# 9xVoice_MikeB_TH_v1.net
KiCad netlist of a schematic drawn in EAGLE
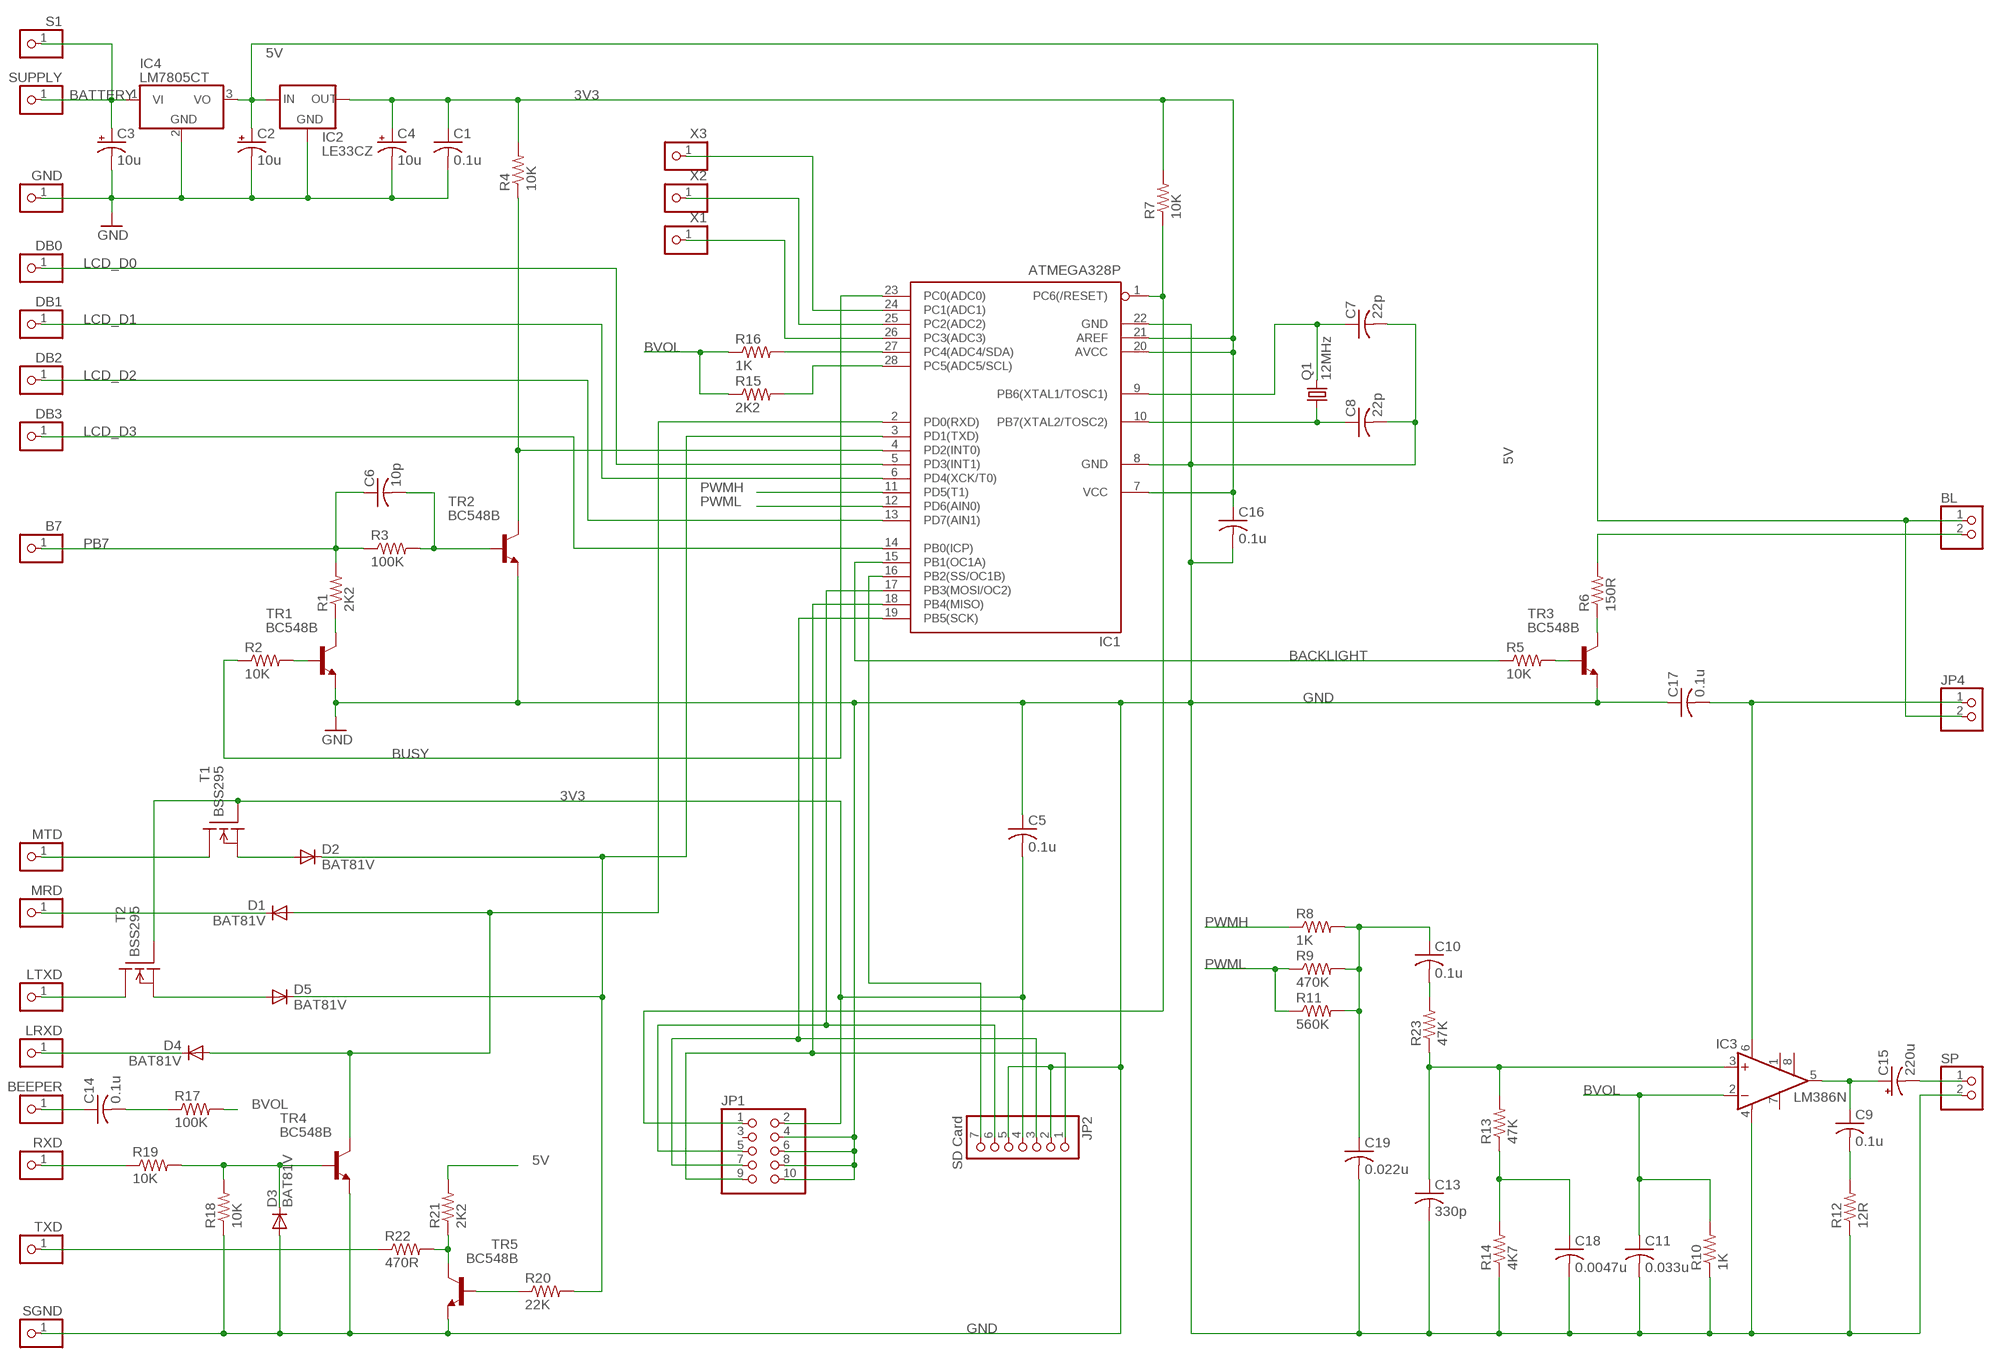
[diagram p0: schematic, sheet 1]

(export (version "E")
  (design (tool "Eeschema 10.0.6"))
  (components
    (comp (ref "B7")
      (value "PINHD-1X1")
      (footprint "eagle-import:1X01")
      (libsource (lib "eagle-import") (part "PINHD-1X1"))
    )
    (comp (ref "BEEPER")
      (value "PINHD-1X1")
      (footprint "eagle-import:1X01")
      (libsource (lib "eagle-import") (part "PINHD-1X1"))
    )
    (comp (ref "BL")
      (value "PINHD-1X2")
      (footprint "eagle-import:1X02")
      (libsource (lib "eagle-import") (part "PINHD-1X2"))
    )
    (comp (ref "C1")
      (value "0.1u")
      (footprint "eagle-import:C025-024X044")
      (libsource (lib "eagle-import") (part "C-US025-024X044"))
    )
    (comp (ref "C2")
      (value "10u")
      (footprint "eagle-import:E1,8-4")
      (libsource (lib "eagle-import") (part "CPOL-USE1.8-4"))
    )
    (comp (ref "C3")
      (value "10u")
      (footprint "eagle-import:E1,8-4")
      (libsource (lib "eagle-import") (part "CPOL-USE1.8-4"))
    )
    (comp (ref "C4")
      (value "10u")
      (footprint "eagle-import:E1,8-4")
      (libsource (lib "eagle-import") (part "CPOL-USE1.8-4"))
    )
    (comp (ref "C5")
      (value "0.1u")
      (footprint "eagle-import:C025-024X044")
      (libsource (lib "eagle-import") (part "C-US025-024X044"))
    )
    (comp (ref "C6")
      (value "10p")
      (footprint "eagle-import:C025-024X044")
      (libsource (lib "eagle-import") (part "C-US025-024X044"))
    )
    (comp (ref "C7")
      (value "22p")
      (footprint "eagle-import:C025-024X044")
      (libsource (lib "eagle-import") (part "C-US025-024X044"))
    )
    (comp (ref "C8")
      (value "22p")
      (footprint "eagle-import:C025-024X044")
      (libsource (lib "eagle-import") (part "C-US025-024X044"))
    )
    (comp (ref "C9")
      (value "0.1u")
      (footprint "eagle-import:C025-024X044")
      (libsource (lib "eagle-import") (part "C-US025-024X044"))
    )
    (comp (ref "C10")
      (value "0.1u")
      (footprint "eagle-import:C025-024X044")
      (libsource (lib "eagle-import") (part "C-US025-024X044"))
    )
    (comp (ref "C11")
      (value "0.033u")
      (footprint "eagle-import:C025-024X044")
      (libsource (lib "eagle-import") (part "C-US025-024X044"))
    )
    (comp (ref "C13")
      (value "330p")
      (footprint "eagle-import:C025-024X044")
      (libsource (lib "eagle-import") (part "C-US025-024X044"))
    )
    (comp (ref "C14")
      (value "0.1u")
      (footprint "eagle-import:C025-024X044")
      (libsource (lib "eagle-import") (part "C-US025-024X044"))
    )
    (comp (ref "C15")
      (value "220u")
      (footprint "eagle-import:E2,5-7")
      (libsource (lib "eagle-import") (part "CPOL-USE2.5-7"))
    )
    (comp (ref "C16")
      (value "0.1u")
      (footprint "eagle-import:C025-024X044")
      (libsource (lib "eagle-import") (part "C-US025-024X044"))
    )
    (comp (ref "C17")
      (value "0.1u")
      (footprint "eagle-import:C025-024X044")
      (libsource (lib "eagle-import") (part "C-US025-024X044"))
    )
    (comp (ref "C18")
      (value "0.0047u")
      (footprint "eagle-import:C025-024X044")
      (libsource (lib "eagle-import") (part "C-US025-024X044"))
    )
    (comp (ref "C19")
      (value "0.022u")
      (footprint "eagle-import:C025-024X044")
      (libsource (lib "eagle-import") (part "C-US025-024X044"))
    )
    (comp (ref "D1")
      (value "BAT81V")
      (footprint "eagle-import:D-2.5")
      (libsource (lib "eagle-import") (part "DIODE-D-2.5"))
    )
    (comp (ref "D2")
      (value "BAT81V")
      (footprint "eagle-import:D-2.5")
      (libsource (lib "eagle-import") (part "DIODE-D-2.5"))
    )
    (comp (ref "D3")
      (value "BAT81V")
      (footprint "eagle-import:D-2.5")
      (libsource (lib "eagle-import") (part "DIODE-D-2.5"))
    )
    (comp (ref "D4")
      (value "BAT81V")
      (footprint "eagle-import:D-2.5")
      (libsource (lib "eagle-import") (part "DIODE-D-2.5"))
    )
    (comp (ref "D5")
      (value "BAT81V")
      (footprint "eagle-import:D-2.5")
      (libsource (lib "eagle-import") (part "DIODE-D-2.5"))
    )
    (comp (ref "DB0")
      (value "PINHD-1X1")
      (footprint "eagle-import:1X01")
      (libsource (lib "eagle-import") (part "PINHD-1X1"))
    )
    (comp (ref "DB1")
      (value "PINHD-1X1")
      (footprint "eagle-import:1X01")
      (libsource (lib "eagle-import") (part "PINHD-1X1"))
    )
    (comp (ref "DB2")
      (value "PINHD-1X1")
      (footprint "eagle-import:1X01")
      (libsource (lib "eagle-import") (part "PINHD-1X1"))
    )
    (comp (ref "DB3")
      (value "PINHD-1X1")
      (footprint "eagle-import:1X01")
      (libsource (lib "eagle-import") (part "PINHD-1X1"))
    )
    (comp (ref "GND")
      (value "PINHD-1X1")
      (footprint "eagle-import:1X01")
      (libsource (lib "eagle-import") (part "PINHD-1X1"))
    )
    (comp (ref "IC1")
      (value "ATMEGA328P")
      (footprint "eagle-import:DIL28-3")
      (libsource (lib "eagle-import") (part "MEGA8-P"))
    )
    (comp (ref "IC2")
      (value "LE33CZ")
      (footprint "eagle-import:78LXX")
      (libsource (lib "eagle-import") (part "78LXX"))
    )
    (comp (ref "IC3")
      (value "LM386N")
      (footprint "eagle-import:DIL08")
      (libsource (lib "eagle-import") (part "LM386?-N1"))
    )
    (comp (ref "IC4")
      (value "LM7805CT")
      (footprint "eagle-import:TO220H")
      (libsource (lib "eagle-import") (part "78T05"))
    )
    (comp (ref "JP1")
      (value "PINHD-2X5")
      (footprint "eagle-import:2X05")
      (libsource (lib "eagle-import") (part "PINHD-2X5"))
    )
    (comp (ref "JP2")
      (value "SD Card")
      (footprint "eagle-import:1X07")
      (libsource (lib "eagle-import") (part "PINHD-1X7"))
    )
    (comp (ref "JP4")
      (value "PINHD-1X2")
      (footprint "eagle-import:1X02")
      (libsource (lib "eagle-import") (part "PINHD-1X2"))
    )
    (comp (ref "LRXD")
      (value "PINHD-1X1")
      (footprint "eagle-import:1X01")
      (libsource (lib "eagle-import") (part "PINHD-1X1"))
    )
    (comp (ref "LTXD")
      (value "PINHD-1X1")
      (footprint "eagle-import:1X01")
      (libsource (lib "eagle-import") (part "PINHD-1X1"))
    )
    (comp (ref "MRD")
      (value "PINHD-1X1")
      (footprint "eagle-import:1X01")
      (libsource (lib "eagle-import") (part "PINHD-1X1"))
    )
    (comp (ref "MTD")
      (value "PINHD-1X1")
      (footprint "eagle-import:1X01")
      (libsource (lib "eagle-import") (part "PINHD-1X1"))
    )
    (comp (ref "Q1")
      (value "12MHz")
      (footprint "eagle-import:HC49_S")
      (libsource (lib "eagle-import") (part "CRYSTALHC49S"))
    )
    (comp (ref "R1")
      (value "2K2")
      (footprint "eagle-import:0207_2V")
      (libsource (lib "eagle-import") (part "R-US_0207/2V"))
    )
    (comp (ref "R2")
      (value "10K")
      (footprint "eagle-import:0207_10")
      (libsource (lib "eagle-import") (part "R-US_0207/10"))
    )
    (comp (ref "R3")
      (value "100K")
      (footprint "eagle-import:0207_2V")
      (libsource (lib "eagle-import") (part "R-US_0207/2V"))
    )
    (comp (ref "R4")
      (value "10K")
      (footprint "eagle-import:0207_2V")
      (libsource (lib "eagle-import") (part "R-US_0207/2V"))
    )
    (comp (ref "R5")
      (value "10K")
      (footprint "eagle-import:0207_2V")
      (libsource (lib "eagle-import") (part "R-US_0207/2V"))
    )
    (comp (ref "R6")
      (value "150R")
      (footprint "eagle-import:0207_2V")
      (libsource (lib "eagle-import") (part "R-US_0207/2V"))
    )
    (comp (ref "R7")
      (value "10K")
      (footprint "eagle-import:0207_2V")
      (libsource (lib "eagle-import") (part "R-US_0207/2V"))
    )
    (comp (ref "R8")
      (value "1K")
      (footprint "eagle-import:0207_2V")
      (libsource (lib "eagle-import") (part "R-US_0207/2V"))
    )
    (comp (ref "R9")
      (value "470K")
      (footprint "eagle-import:0207_2V")
      (libsource (lib "eagle-import") (part "R-US_0207/2V"))
    )
    (comp (ref "R10")
      (value "1K")
      (footprint "eagle-import:0207_2V")
      (libsource (lib "eagle-import") (part "R-US_0207/2V"))
    )
    (comp (ref "R11")
      (value "560K")
      (footprint "eagle-import:0207_2V")
      (libsource (lib "eagle-import") (part "R-US_0207/2V"))
    )
    (comp (ref "R12")
      (value "12R")
      (footprint "eagle-import:0207_2V")
      (libsource (lib "eagle-import") (part "R-US_0207/2V"))
    )
    (comp (ref "R13")
      (value "47K")
      (footprint "eagle-import:0207_2V")
      (libsource (lib "eagle-import") (part "R-US_0207/2V"))
    )
    (comp (ref "R14")
      (value "4K7")
      (footprint "eagle-import:0207_2V")
      (libsource (lib "eagle-import") (part "R-US_0207/2V"))
    )
    (comp (ref "R15")
      (value "2K2")
      (footprint "eagle-import:0207_2V")
      (libsource (lib "eagle-import") (part "R-US_0207/2V"))
    )
    (comp (ref "R16")
      (value "1K")
      (footprint "eagle-import:0207_2V")
      (libsource (lib "eagle-import") (part "R-US_0207/2V"))
    )
    (comp (ref "R17")
      (value "100K")
      (footprint "eagle-import:0207_2V")
      (libsource (lib "eagle-import") (part "R-US_0207/2V"))
    )
    (comp (ref "R18")
      (value "10K")
      (footprint "eagle-import:0207_2V")
      (libsource (lib "eagle-import") (part "R-US_0207/2V"))
    )
    (comp (ref "R19")
      (value "10K")
      (footprint "eagle-import:0207_2V")
      (libsource (lib "eagle-import") (part "R-US_0207/2V"))
    )
    (comp (ref "R20")
      (value "22K")
      (footprint "eagle-import:0207_2V")
      (libsource (lib "eagle-import") (part "R-US_0207/2V"))
    )
    (comp (ref "R21")
      (value "2K2")
      (footprint "eagle-import:0207_2V")
      (libsource (lib "eagle-import") (part "R-US_0207/2V"))
    )
    (comp (ref "R22")
      (value "470R")
      (footprint "eagle-import:0207_2V")
      (libsource (lib "eagle-import") (part "R-US_0207/2V"))
    )
    (comp (ref "R23")
      (value "47K")
      (footprint "eagle-import:0207_2V")
      (libsource (lib "eagle-import") (part "R-US_0207/2V"))
    )
    (comp (ref "RXD")
      (value "PINHD-1X1")
      (footprint "eagle-import:1X01")
      (libsource (lib "eagle-import") (part "PINHD-1X1"))
    )
    (comp (ref "S1")
      (value "PINHD-1X1")
      (footprint "eagle-import:1X01")
      (libsource (lib "eagle-import") (part "PINHD-1X1"))
    )
    (comp (ref "SGND")
      (value "PINHD-1X1")
      (footprint "eagle-import:1X01")
      (libsource (lib "eagle-import") (part "PINHD-1X1"))
    )
    (comp (ref "SP")
      (value "PINHD-1X2")
      (footprint "eagle-import:1X02")
      (libsource (lib "eagle-import") (part "PINHD-1X2"))
    )
    (comp (ref "SUPPLY")
      (value "PINHD-1X1")
      (footprint "eagle-import:1X01")
      (libsource (lib "eagle-import") (part "PINHD-1X1"))
    )
    (comp (ref "T1")
      (value "BSS295")
      (footprint "eagle-import:TO92")
      (libsource (lib "eagle-import") (part "BSS295"))
    )
    (comp (ref "T2")
      (value "BSS295")
      (footprint "eagle-import:TO92")
      (libsource (lib "eagle-import") (part "BSS295"))
    )
    (comp (ref "TR1")
      (value "BC548B")
      (footprint "eagle-import:TO92-EBC")
      (libsource (lib "eagle-import") (part "BC548B"))
    )
    (comp (ref "TR2")
      (value "BC548B")
      (footprint "eagle-import:TO92-EBC")
      (libsource (lib "eagle-import") (part "BC548B"))
    )
    (comp (ref "TR3")
      (value "BC548B")
      (footprint "eagle-import:TO92-EBC")
      (libsource (lib "eagle-import") (part "BC548B"))
    )
    (comp (ref "TR4")
      (value "BC548B")
      (footprint "eagle-import:TO92-EBC")
      (libsource (lib "eagle-import") (part "BC548B"))
    )
    (comp (ref "TR5")
      (value "BC548B")
      (footprint "eagle-import:TO92-EBC")
      (libsource (lib "eagle-import") (part "BC548B"))
    )
    (comp (ref "TXD")
      (value "PINHD-1X1")
      (footprint "eagle-import:1X01")
      (libsource (lib "eagle-import") (part "PINHD-1X1"))
    )
    (comp (ref "X1")
      (value "PINHD-1X1")
      (footprint "eagle-import:1X01")
      (libsource (lib "eagle-import") (part "PINHD-1X1"))
    )
    (comp (ref "X2")
      (value "PINHD-1X1")
      (footprint "eagle-import:1X01")
      (libsource (lib "eagle-import") (part "PINHD-1X1"))
    )
    (comp (ref "X3")
      (value "PINHD-1X1")
      (footprint "eagle-import:1X01")
      (libsource (lib "eagle-import") (part "PINHD-1X1"))
    )
  )
  (nets
    (net (code "1") (name "/3V3") (class "Default")
      (node (ref "C1") (pin "1") (pinfunction "1_1") (pintype "passive"))
      (node (ref "C16") (pin "1") (pinfunction "1_1") (pintype "passive"))
      (node (ref "C4") (pin "+") (pinfunction "+_+") (pintype "passive"))
      (node (ref "C5") (pin "2") (pinfunction "2_2") (pintype "passive"))
      (node (ref "IC1") (pin "20") (pinfunction "AVCC_20") (pintype "power_in"))
      (node (ref "IC1") (pin "21") (pinfunction "AREF_21") (pintype "passive"))
      (node (ref "IC1") (pin "7") (pinfunction "VCC_7") (pintype "power_in"))
      (node (ref "IC2") (pin "OUT") (pinfunction "OUT_OUT") (pintype "passive"))
      (node (ref "JP1") (pin "2") (pinfunction "2_2") (pintype "passive"))
      (node (ref "JP2") (pin "4") (pinfunction "4_4") (pintype "passive"))
      (node (ref "R4") (pin "2") (pinfunction "2_2") (pintype "passive"))
      (node (ref "R7") (pin "2") (pinfunction "2_2") (pintype "passive"))
      (node (ref "T1") (pin "1") (pinfunction "G_1") (pintype "passive"))
      (node (ref "T2") (pin "1") (pinfunction "G_1") (pintype "passive"))
    )
    (net (code "2") (name "/5V") (class "Default")
      (node (ref "BL") (pin "1") (pinfunction "1_1") (pintype "passive"))
      (node (ref "C2") (pin "+") (pinfunction "+_+") (pintype "passive"))
      (node (ref "IC2") (pin "IN") (pinfunction "IN_IN") (pintype "input"))
      (node (ref "IC4") (pin "3") (pinfunction "VO_3") (pintype "passive"))
      (node (ref "JP4") (pin "2") (pinfunction "2_2") (pintype "passive"))
      (node (ref "R21") (pin "2") (pinfunction "2_2") (pintype "passive"))
    )
    (net (code "3") (name "/BACKLIGHT") (class "Default")
      (node (ref "IC1") (pin "15") (pinfunction "PB1(OC1A)_15") (pintype "bidirectional"))
      (node (ref "R5") (pin "1") (pinfunction "1_1") (pintype "passive"))
    )
    (net (code "4") (name "/BATTERY") (class "Default")
      (node (ref "C3") (pin "+") (pinfunction "+_+") (pintype "passive"))
      (node (ref "IC4") (pin "1") (pinfunction "VI_1") (pintype "input"))
      (node (ref "S1") (pin "1") (pinfunction "1_1") (pintype "passive"))
      (node (ref "SUPPLY") (pin "1") (pinfunction "1_1") (pintype "passive"))
    )
    (net (code "5") (name "/BUSY") (class "Default")
      (node (ref "IC1") (pin "23") (pinfunction "PC0(ADC0)_23") (pintype "bidirectional"))
      (node (ref "R2") (pin "1") (pinfunction "1_1") (pintype "passive"))
    )
    (net (code "6") (name "/BVOL") (class "Default")
      (node (ref "C11") (pin "1") (pinfunction "1_1") (pintype "passive"))
      (node (ref "IC3") (pin "2") (pinfunction "-IN_2") (pintype "input"))
      (node (ref "R10") (pin "2") (pinfunction "2_2") (pintype "passive"))
      (node (ref "R15") (pin "1") (pinfunction "1_1") (pintype "passive"))
      (node (ref "R16") (pin "1") (pinfunction "1_1") (pintype "passive"))
      (node (ref "R17") (pin "2") (pinfunction "2_2") (pintype "passive"))
    )
    (net (code "7") (name "/LCD_D0") (class "Default")
      (node (ref "DB0") (pin "1") (pinfunction "1_1") (pintype "passive"))
      (node (ref "IC1") (pin "5") (pinfunction "PD3(INT1)_5") (pintype "bidirectional"))
    )
    (net (code "8") (name "/LCD_D1") (class "Default")
      (node (ref "DB1") (pin "1") (pinfunction "1_1") (pintype "passive"))
      (node (ref "IC1") (pin "6") (pinfunction "PD4(XCK/T0)_6") (pintype "bidirectional"))
    )
    (net (code "9") (name "/LCD_D2") (class "Default")
      (node (ref "DB2") (pin "1") (pinfunction "1_1") (pintype "passive"))
      (node (ref "IC1") (pin "13") (pinfunction "PD7(AIN1)_13") (pintype "bidirectional"))
    )
    (net (code "10") (name "/LCD_D3") (class "Default")
      (node (ref "DB3") (pin "1") (pinfunction "1_1") (pintype "passive"))
      (node (ref "IC1") (pin "14") (pinfunction "PB0(ICP)_14") (pintype "bidirectional"))
    )
    (net (code "11") (name "/PB7") (class "Default")
      (node (ref "B7") (pin "1") (pinfunction "1_1") (pintype "passive"))
      (node (ref "C6") (pin "1") (pinfunction "1_1") (pintype "passive"))
      (node (ref "R1") (pin "2") (pinfunction "2_2") (pintype "passive"))
      (node (ref "R3") (pin "1") (pinfunction "1_1") (pintype "passive"))
    )
    (net (code "12") (name "/PWMH") (class "Default")
      (node (ref "IC1") (pin "11") (pinfunction "PD5(T1)_11") (pintype "bidirectional"))
      (node (ref "R8") (pin "1") (pinfunction "1_1") (pintype "passive"))
    )
    (net (code "13") (name "/PWML") (class "Default")
      (node (ref "IC1") (pin "12") (pinfunction "PD6(AIN0)_12") (pintype "bidirectional"))
      (node (ref "R11") (pin "1") (pinfunction "1_1") (pintype "passive"))
      (node (ref "R9") (pin "1") (pinfunction "1_1") (pintype "passive"))
    )
    (net (code "14") (name "GND") (class "Default")
      (node (ref "C1") (pin "2") (pinfunction "2_2") (pintype "passive"))
      (node (ref "C11") (pin "2") (pinfunction "2_2") (pintype "passive"))
      (node (ref "C13") (pin "2") (pinfunction "2_2") (pintype "passive"))
      (node (ref "C16") (pin "2") (pinfunction "2_2") (pintype "passive"))
      (node (ref "C17") (pin "1") (pinfunction "1_1") (pintype "passive"))
      (node (ref "C18") (pin "2") (pinfunction "2_2") (pintype "passive"))
      (node (ref "C19") (pin "2") (pinfunction "2_2") (pintype "passive"))
      (node (ref "C2") (pin "-") (pinfunction "-_-") (pintype "passive"))
      (node (ref "C3") (pin "-") (pinfunction "-_-") (pintype "passive"))
      (node (ref "C4") (pin "-") (pinfunction "-_-") (pintype "passive"))
      (node (ref "C5") (pin "1") (pinfunction "1_1") (pintype "passive"))
      (node (ref "C7") (pin "2") (pinfunction "2_2") (pintype "passive"))
      (node (ref "C8") (pin "2") (pinfunction "2_2") (pintype "passive"))
      (node (ref "D3") (pin "A") (pinfunction "A_A") (pintype "passive"))
      (node (ref "GND") (pin "1") (pinfunction "1_1") (pintype "passive"))
      (node (ref "IC1") (pin "22") (pinfunction "GND_22") (pintype "power_in"))
      (node (ref "IC1") (pin "8") (pinfunction "GND_8") (pintype "power_in"))
      (node (ref "IC2") (pin "GND") (pinfunction "GND_GND") (pintype "input"))
      (node (ref "IC3") (pin "4") (pinfunction "GND_4") (pintype "power_in"))
      (node (ref "IC4") (pin "2") (pinfunction "GND_2") (pintype "passive"))
      (node (ref "JP1") (pin "10") (pinfunction "10_10") (pintype "passive"))
      (node (ref "JP1") (pin "4") (pinfunction "4_4") (pintype "passive"))
      (node (ref "JP1") (pin "6") (pinfunction "6_6") (pintype "passive"))
      (node (ref "JP1") (pin "8") (pinfunction "8_8") (pintype "passive"))
      (node (ref "JP2") (pin "2") (pinfunction "2_2") (pintype "passive"))
      (node (ref "JP2") (pin "5") (pinfunction "5_5") (pintype "passive"))
      (node (ref "R10") (pin "1") (pinfunction "1_1") (pintype "passive"))
      (node (ref "R12") (pin "1") (pinfunction "1_1") (pintype "passive"))
      (node (ref "R14") (pin "1") (pinfunction "1_1") (pintype "passive"))
      (node (ref "R18") (pin "1") (pinfunction "1_1") (pintype "passive"))
      (node (ref "SGND") (pin "1") (pinfunction "1_1") (pintype "passive"))
      (node (ref "SP") (pin "2") (pinfunction "2_2") (pintype "passive"))
      (node (ref "TR1") (pin "E") (pinfunction "E_E") (pintype "passive"))
      (node (ref "TR2") (pin "E") (pinfunction "E_E") (pintype "passive"))
      (node (ref "TR3") (pin "E") (pinfunction "E_E") (pintype "passive"))
      (node (ref "TR4") (pin "E") (pinfunction "E_E") (pintype "passive"))
      (node (ref "TR5") (pin "E") (pinfunction "E_E") (pintype "passive"))
    )
    (net (code "15") (name "Net-(BEEPER-Pad1)") (class "Default")
      (node (ref "BEEPER") (pin "1") (pinfunction "1_1") (pintype "passive"))
      (node (ref "C14") (pin "1") (pinfunction "1_1") (pintype "passive"))
    )
    (net (code "16") (name "Net-(BL-Pad2)") (class "Default")
      (node (ref "BL") (pin "2") (pinfunction "2_2") (pintype "passive"))
      (node (ref "R6") (pin "2") (pinfunction "2_2") (pintype "passive"))
    )
    (net (code "17") (name "Net-(C6-Pad2)") (class "Default")
      (node (ref "C6") (pin "2") (pinfunction "2_2") (pintype "passive"))
      (node (ref "R3") (pin "2") (pinfunction "2_2") (pintype "passive"))
      (node (ref "TR2") (pin "B") (pinfunction "B_B") (pintype "passive"))
    )
    (net (code "18") (name "Net-(C9-Pad2)") (class "Default")
      (node (ref "C9") (pin "2") (pinfunction "2_2") (pintype "passive"))
      (node (ref "R12") (pin "2") (pinfunction "2_2") (pintype "passive"))
    )
    (net (code "19") (name "Net-(C10-Pad1)") (class "Default")
      (node (ref "C10") (pin "1") (pinfunction "1_1") (pintype "passive"))
      (node (ref "C19") (pin "1") (pinfunction "1_1") (pintype "passive"))
      (node (ref "R11") (pin "2") (pinfunction "2_2") (pintype "passive"))
      (node (ref "R8") (pin "2") (pinfunction "2_2") (pintype "passive"))
      (node (ref "R9") (pin "2") (pinfunction "2_2") (pintype "passive"))
    )
    (net (code "20") (name "Net-(C10-Pad2)") (class "Default")
      (node (ref "C10") (pin "2") (pinfunction "2_2") (pintype "passive"))
      (node (ref "R23") (pin "2") (pinfunction "2_2") (pintype "passive"))
    )
    (net (code "21") (name "Net-(C14-Pad2)") (class "Default")
      (node (ref "C14") (pin "2") (pinfunction "2_2") (pintype "passive"))
      (node (ref "R17") (pin "1") (pinfunction "1_1") (pintype "passive"))
    )
    (net (code "22") (name "Net-(C15-Pad-)") (class "Default")
      (node (ref "C15") (pin "-") (pinfunction "-_-") (pintype "passive"))
      (node (ref "SP") (pin "1") (pinfunction "1_1") (pintype "passive"))
    )
    (net (code "23") (name "Net-(C18-Pad1)") (class "Default")
      (node (ref "C18") (pin "1") (pinfunction "1_1") (pintype "passive"))
      (node (ref "R13") (pin "1") (pinfunction "1_1") (pintype "passive"))
      (node (ref "R14") (pin "2") (pinfunction "2_2") (pintype "passive"))
    )
    (net (code "24") (name "Net-(D1-PadC)") (class "Default")
      (node (ref "D1") (pin "C") (pinfunction "C_C") (pintype "passive"))
      (node (ref "MRD") (pin "1") (pinfunction "1_1") (pintype "passive"))
    )
    (net (code "25") (name "Net-(D3-PadC)") (class "Default")
      (node (ref "D3") (pin "C") (pinfunction "C_C") (pintype "passive"))
      (node (ref "R18") (pin "2") (pinfunction "2_2") (pintype "passive"))
      (node (ref "R19") (pin "2") (pinfunction "2_2") (pintype "passive"))
      (node (ref "TR4") (pin "B") (pinfunction "B_B") (pintype "passive"))
    )
    (net (code "26") (name "Net-(D4-PadC)") (class "Default")
      (node (ref "D4") (pin "C") (pinfunction "C_C") (pintype "passive"))
      (node (ref "LRXD") (pin "1") (pinfunction "1_1") (pintype "passive"))
    )
    (net (code "27") (name "Net-(IC1-PB2(SS{slash}OC1B))") (class "Default")
      (node (ref "IC1") (pin "16") (pinfunction "PB2(SS/OC1B)_16") (pintype "bidirectional"))
      (node (ref "JP2") (pin "7") (pinfunction "7_7") (pintype "passive"))
    )
    (net (code "28") (name "Net-(IC1-PB3(MOSI{slash}OC2))") (class "Default")
      (node (ref "IC1") (pin "17") (pinfunction "PB3(MOSI/OC2)_17") (pintype "bidirectional"))
      (node (ref "JP1") (pin "5") (pinfunction "5_5") (pintype "passive"))
      (node (ref "JP2") (pin "6") (pinfunction "6_6") (pintype "passive"))
    )
    (net (code "29") (name "Net-(IC1-PB4(MISO))") (class "Default")
      (node (ref "IC1") (pin "18") (pinfunction "PB4(MISO)_18") (pintype "bidirectional"))
      (node (ref "JP1") (pin "9") (pinfunction "9_9") (pintype "passive"))
      (node (ref "JP2") (pin "1") (pinfunction "1_1") (pintype "passive"))
    )
    (net (code "30") (name "Net-(IC1-PB5(SCK))") (class "Default")
      (node (ref "IC1") (pin "19") (pinfunction "PB5(SCK)_19") (pintype "bidirectional"))
      (node (ref "JP1") (pin "7") (pinfunction "7_7") (pintype "passive"))
      (node (ref "JP2") (pin "3") (pinfunction "3_3") (pintype "passive"))
    )
    (net (code "31") (name "Net-(IC1-PB6(XTAL1{slash}TOSC1))") (class "Default")
      (node (ref "C7") (pin "1") (pinfunction "1_1") (pintype "passive"))
      (node (ref "IC1") (pin "9") (pinfunction "PB6(XTAL1/TOSC1)_9") (pintype "bidirectional"))
      (node (ref "Q1") (pin "2") (pinfunction "2_2") (pintype "passive"))
    )
    (net (code "32") (name "Net-(IC1-PB7(XTAL2{slash}TOSC2))") (class "Default")
      (node (ref "C8") (pin "1") (pinfunction "1_1") (pintype "passive"))
      (node (ref "IC1") (pin "10") (pinfunction "PB7(XTAL2/TOSC2)_10") (pintype "bidirectional"))
      (node (ref "Q1") (pin "1") (pinfunction "1_1") (pintype "passive"))
    )
    (net (code "33") (name "Net-(IC1-PC1(ADC1))") (class "Default")
      (node (ref "IC1") (pin "24") (pinfunction "PC1(ADC1)_24") (pintype "bidirectional"))
      (node (ref "X3") (pin "1") (pinfunction "1_1") (pintype "passive"))
    )
    (net (code "34") (name "Net-(IC1-PC2(ADC2))") (class "Default")
      (node (ref "IC1") (pin "25") (pinfunction "PC2(ADC2)_25") (pintype "bidirectional"))
      (node (ref "X2") (pin "1") (pinfunction "1_1") (pintype "passive"))
    )
    (net (code "35") (name "Net-(IC1-PC3(ADC3))") (class "Default")
      (node (ref "IC1") (pin "26") (pinfunction "PC3(ADC3)_26") (pintype "bidirectional"))
      (node (ref "X1") (pin "1") (pinfunction "1_1") (pintype "passive"))
    )
    (net (code "36") (name "Net-(IC1-PC4(ADC4{slash}SDA))") (class "Default")
      (node (ref "IC1") (pin "27") (pinfunction "PC4(ADC4/SDA)_27") (pintype "bidirectional"))
      (node (ref "R16") (pin "2") (pinfunction "2_2") (pintype "passive"))
    )
    (net (code "37") (name "Net-(IC1-PC5(ADC5{slash}SCL))") (class "Default")
      (node (ref "IC1") (pin "28") (pinfunction "PC5(ADC5/SCL)_28") (pintype "bidirectional"))
      (node (ref "R15") (pin "2") (pinfunction "2_2") (pintype "passive"))
    )
    (net (code "38") (name "Net-(IC1-PC6({slash}RESET))") (class "Default")
      (node (ref "IC1") (pin "1") (pinfunction "PC6(/RESET)_1") (pintype "bidirectional"))
      (node (ref "JP1") (pin "1") (pinfunction "1_1") (pintype "passive"))
      (node (ref "R7") (pin "1") (pinfunction "1_1") (pintype "passive"))
    )
    (net (code "39") (name "Net-(IC1-PD0(RXD))") (class "Default")
      (node (ref "D1") (pin "A") (pinfunction "A_A") (pintype "passive"))
      (node (ref "D4") (pin "A") (pinfunction "A_A") (pintype "passive"))
      (node (ref "IC1") (pin "2") (pinfunction "PD0(RXD)_2") (pintype "bidirectional"))
      (node (ref "TR4") (pin "C") (pinfunction "C_C") (pintype "passive"))
    )
    (net (code "40") (name "Net-(IC1-PD1(TXD))") (class "Default")
      (node (ref "D2") (pin "C") (pinfunction "C_C") (pintype "passive"))
      (node (ref "D5") (pin "C") (pinfunction "C_C") (pintype "passive"))
      (node (ref "IC1") (pin "3") (pinfunction "PD1(TXD)_3") (pintype "bidirectional"))
      (node (ref "R20") (pin "2") (pinfunction "2_2") (pintype "passive"))
    )
    (net (code "41") (name "Net-(IC1-PD2(INT0))") (class "Default")
      (node (ref "IC1") (pin "4") (pinfunction "PD2(INT0)_4") (pintype "bidirectional"))
      (node (ref "R4") (pin "1") (pinfunction "1_1") (pintype "passive"))
      (node (ref "TR2") (pin "C") (pinfunction "C_C") (pintype "passive"))
    )
    (net (code "42") (name "Net-(IC3-+IN)") (class "Default")
      (node (ref "C13") (pin "1") (pinfunction "1_1") (pintype "passive"))
      (node (ref "IC3") (pin "3") (pinfunction "+IN_3") (pintype "input"))
      (node (ref "R13") (pin "2") (pinfunction "2_2") (pintype "passive"))
      (node (ref "R23") (pin "1") (pinfunction "1_1") (pintype "passive"))
    )
    (net (code "43") (name "Net-(IC3-OUT)") (class "Default")
      (node (ref "C15") (pin "+") (pinfunction "+_+") (pintype "passive"))
      (node (ref "C9") (pin "1") (pinfunction "1_1") (pintype "passive"))
      (node (ref "IC3") (pin "5") (pinfunction "OUT_5") (pintype "output"))
    )
    (net (code "44") (name "Net-(IC3-VS)") (class "Default")
      (node (ref "C17") (pin "2") (pinfunction "2_2") (pintype "passive"))
      (node (ref "IC3") (pin "6") (pinfunction "VS_6") (pintype "power_in"))
      (node (ref "JP4") (pin "1") (pinfunction "1_1") (pintype "passive"))
    )
    (net (code "45") (name "Net-(R1-Pad1)") (class "Default")
      (node (ref "R1") (pin "1") (pinfunction "1_1") (pintype "passive"))
      (node (ref "TR1") (pin "C") (pinfunction "C_C") (pintype "passive"))
    )
    (net (code "46") (name "Net-(R2-Pad2)") (class "Default")
      (node (ref "R2") (pin "2") (pinfunction "2_2") (pintype "passive"))
      (node (ref "TR1") (pin "B") (pinfunction "B_B") (pintype "passive"))
    )
    (net (code "47") (name "Net-(R5-Pad2)") (class "Default")
      (node (ref "R5") (pin "2") (pinfunction "2_2") (pintype "passive"))
      (node (ref "TR3") (pin "B") (pinfunction "B_B") (pintype "passive"))
    )
    (net (code "48") (name "Net-(R6-Pad1)") (class "Default")
      (node (ref "R6") (pin "1") (pinfunction "1_1") (pintype "passive"))
      (node (ref "TR3") (pin "C") (pinfunction "C_C") (pintype "passive"))
    )
    (net (code "49") (name "Net-(R19-Pad1)") (class "Default")
      (node (ref "R19") (pin "1") (pinfunction "1_1") (pintype "passive"))
      (node (ref "RXD") (pin "1") (pinfunction "1_1") (pintype "passive"))
    )
    (net (code "50") (name "Net-(R20-Pad1)") (class "Default")
      (node (ref "R20") (pin "1") (pinfunction "1_1") (pintype "passive"))
      (node (ref "TR5") (pin "B") (pinfunction "B_B") (pintype "passive"))
    )
    (net (code "51") (name "Net-(R21-Pad1)") (class "Default")
      (node (ref "R21") (pin "1") (pinfunction "1_1") (pintype "passive"))
      (node (ref "R22") (pin "2") (pinfunction "2_2") (pintype "passive"))
      (node (ref "TR5") (pin "C") (pinfunction "C_C") (pintype "passive"))
    )
    (net (code "52") (name "Net-(R22-Pad1)") (class "Default")
      (node (ref "R22") (pin "1") (pinfunction "1_1") (pintype "passive"))
      (node (ref "TXD") (pin "1") (pinfunction "1_1") (pintype "passive"))
    )
    (net (code "53") (name "Net-(T1-D)") (class "Default")
      (node (ref "MTD") (pin "1") (pinfunction "1_1") (pintype "passive"))
      (node (ref "T1") (pin "2") (pinfunction "D_2") (pintype "passive"))
    )
    (net (code "54") (name "Net-(T1-S)") (class "Default")
      (node (ref "D2") (pin "A") (pinfunction "A_A") (pintype "passive"))
      (node (ref "T1") (pin "3") (pinfunction "S_3") (pintype "passive"))
    )
    (net (code "55") (name "Net-(T2-D)") (class "Default")
      (node (ref "LTXD") (pin "1") (pinfunction "1_1") (pintype "passive"))
      (node (ref "T2") (pin "2") (pinfunction "D_2") (pintype "passive"))
    )
    (net (code "56") (name "Net-(T2-S)") (class "Default")
      (node (ref "D5") (pin "A") (pinfunction "A_A") (pintype "passive"))
      (node (ref "T2") (pin "3") (pinfunction "S_3") (pintype "passive"))
    )
    (net (code "57") (name "unconnected-(IC3-BYPASS-Pad7)") (class "Default")
      (node (ref "IC3") (pin "7") (pinfunction "BYPASS_7") (pintype "passive"))
    )
    (net (code "58") (name "unconnected-(IC3-GAIN-Pad1)") (class "Default")
      (node (ref "IC3") (pin "1") (pinfunction "GAIN_1") (pintype "passive"))
    )
    (net (code "59") (name "unconnected-(IC3-GAIN-Pad8)") (class "Default")
      (node (ref "IC3") (pin "8") (pinfunction "GAIN_8") (pintype "passive"))
    )
    (net (code "60") (name "unconnected-(JP1-Pad3)") (class "Default")
      (node (ref "JP1") (pin "3") (pinfunction "3_3") (pintype "passive"))
    )
  )
)
